# Autouke_Schematic.net
KiCad netlist of a schematic drawn in EAGLE
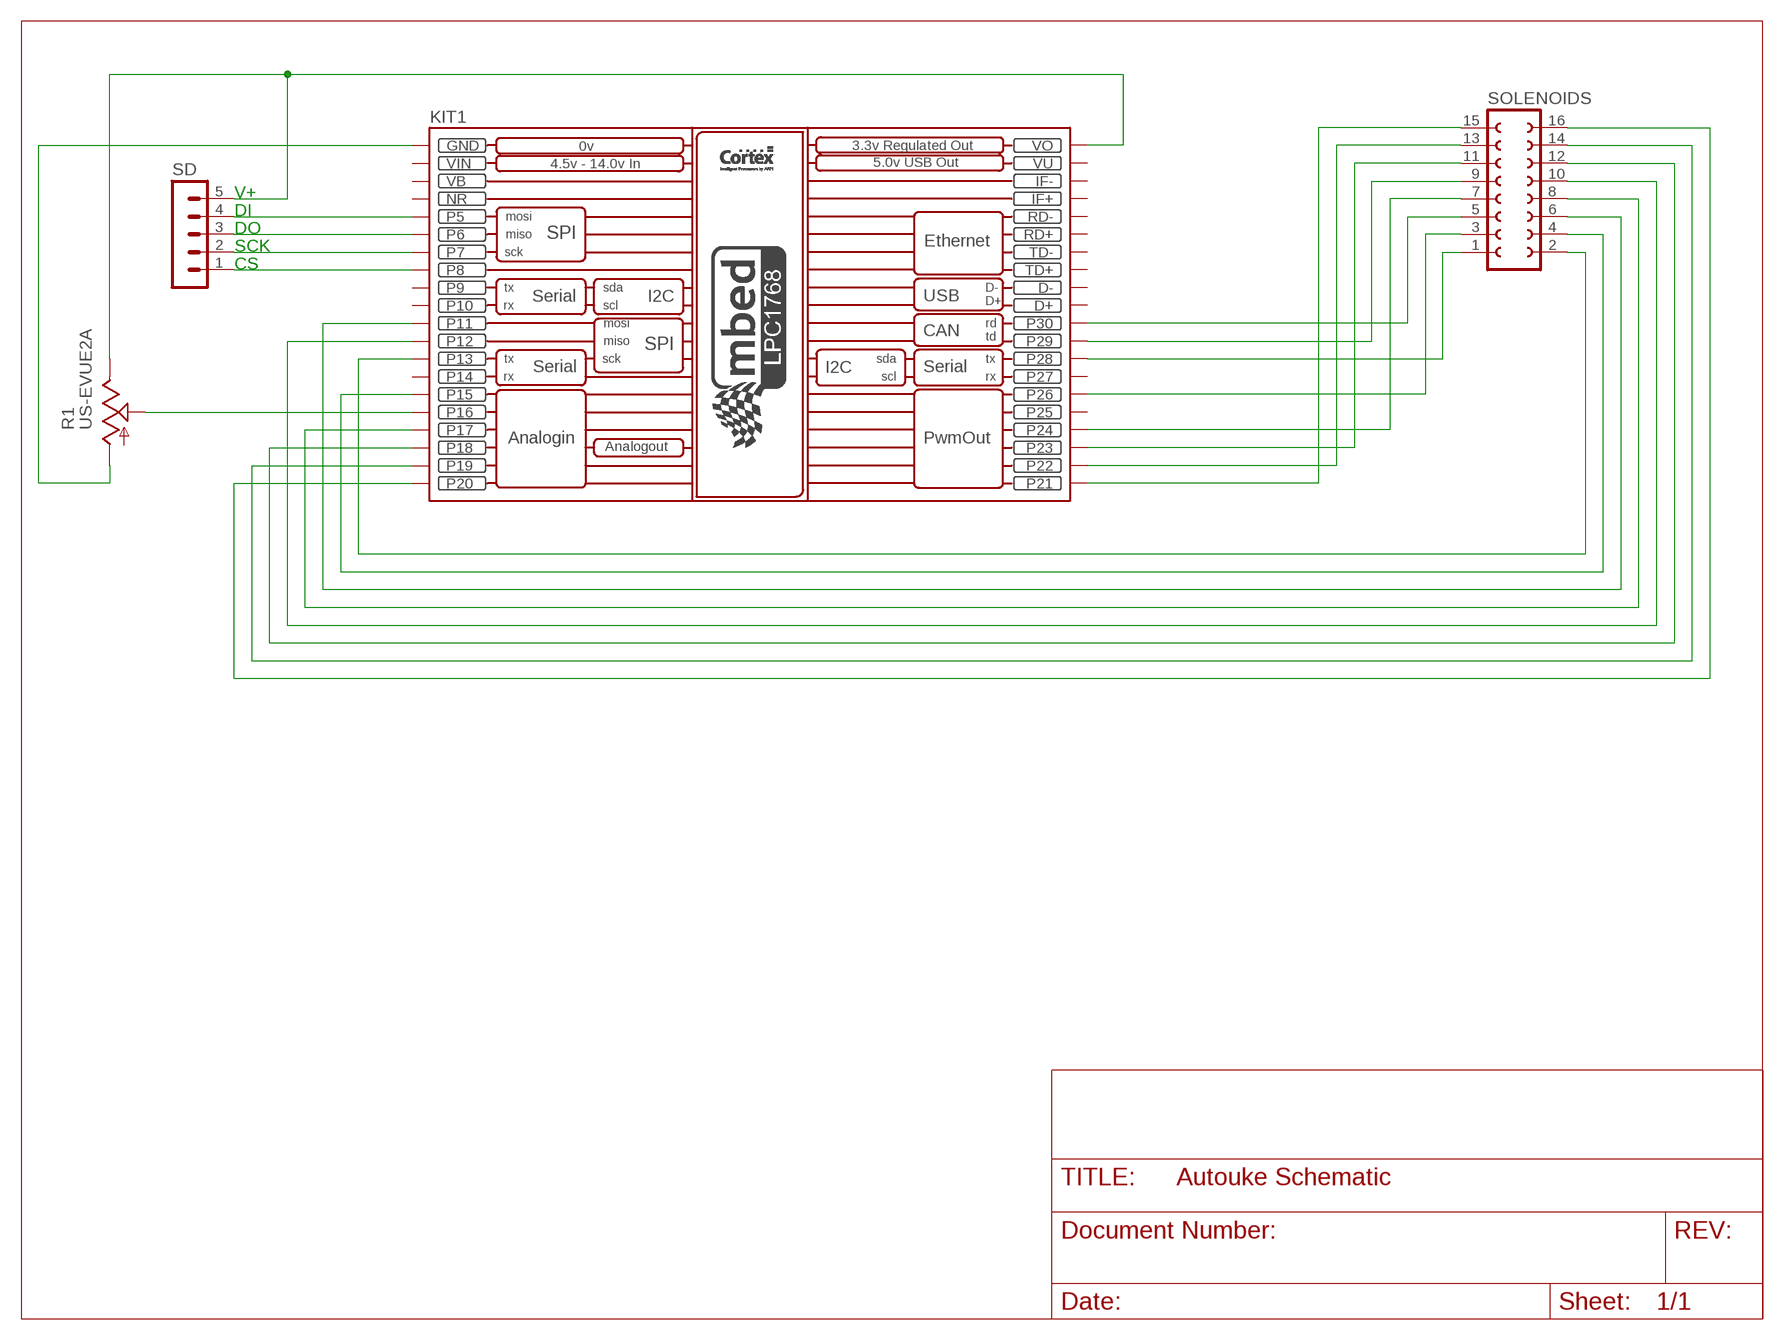
[diagram p0: schematic, sheet 1]

(export (version "E")
  (design (tool "Eeschema 10.0.6"))
  (components
    (comp (ref "KIT1")
      (value "MBED_NXP_LPC1768")
      (footprint "eagle-import:MBED-KIT")
      (libsource (lib "eagle-import") (part "MBED_NXP_LPC1768"))
    )
    (comp (ref "R1")
      (value "US-EVUE2A")
      (footprint "eagle-import:EVUE")
      (libsource (lib "eagle-import") (part "US-EVUE2A"))
    )
    (comp (ref "SD")
      (value "MA05-1")
      (footprint "eagle-import:MA05-1")
      (libsource (lib "eagle-import") (part "MA05-1"))
    )
    (comp (ref "SOLENOIDS")
      (value "FE08-2")
      (footprint "eagle-import:FE08-2")
      (libsource (lib "eagle-import") (part "FE08-2"))
    )
  )
  (nets
    (net (code "1") (name "/NR") (class "Default")
      (node (ref "KIT1") (pin "NR") (pinfunction "NR_NR") (pintype "power_in"))
    )
    (net (code "2") (name "/VB") (class "Default")
      (node (ref "KIT1") (pin "VB") (pinfunction "VB_VB") (pintype "power_in"))
    )
    (net (code "3") (name "/VIN") (class "Default")
      (node (ref "KIT1") (pin "VIN") (pinfunction "VIN_VIN") (pintype "power_in"))
    )
    (net (code "4") (name "/VU") (class "Default")
      (node (ref "KIT1") (pin "VU") (pinfunction "VU_VU") (pintype "power_in"))
    )
    (net (code "5") (name "Net-(KIT1-P5)") (class "Default")
      (node (ref "KIT1") (pin "P$5") (pinfunction "P5_P$5") (pintype "bidirectional"))
      (node (ref "SD") (pin "4") (pinfunction "4_4") (pintype "passive"))
    )
    (net (code "6") (name "Net-(KIT1-P6)") (class "Default")
      (node (ref "KIT1") (pin "P$6") (pinfunction "P6_P$6") (pintype "bidirectional"))
      (node (ref "SD") (pin "3") (pinfunction "3_3") (pintype "passive"))
    )
    (net (code "7") (name "Net-(KIT1-P7)") (class "Default")
      (node (ref "KIT1") (pin "P$7") (pinfunction "P7_P$7") (pintype "bidirectional"))
      (node (ref "SD") (pin "2") (pinfunction "2_2") (pintype "passive"))
    )
    (net (code "8") (name "Net-(KIT1-P8)") (class "Default")
      (node (ref "KIT1") (pin "P$8") (pinfunction "P8_P$8") (pintype "bidirectional"))
      (node (ref "SD") (pin "1") (pinfunction "1_1") (pintype "passive"))
    )
    (net (code "9") (name "Net-(KIT1-P11)") (class "Default")
      (node (ref "KIT1") (pin "P$11") (pinfunction "P11_P$11") (pintype "bidirectional"))
      (node (ref "SOLENOIDS") (pin "6") (pinfunction "6_6") (pintype "passive"))
    )
    (net (code "10") (name "Net-(KIT1-P12)") (class "Default")
      (node (ref "KIT1") (pin "P$12") (pinfunction "P12_P$12") (pintype "bidirectional"))
      (node (ref "SOLENOIDS") (pin "10") (pinfunction "10_10") (pintype "passive"))
    )
    (net (code "11") (name "Net-(KIT1-P13)") (class "Default")
      (node (ref "KIT1") (pin "P$13") (pinfunction "P13_P$13") (pintype "bidirectional"))
      (node (ref "SOLENOIDS") (pin "2") (pinfunction "2_2") (pintype "passive"))
    )
    (net (code "12") (name "Net-(KIT1-P15)") (class "Default")
      (node (ref "KIT1") (pin "P$15") (pinfunction "P15_P$15") (pintype "bidirectional"))
      (node (ref "SOLENOIDS") (pin "4") (pinfunction "4_4") (pintype "passive"))
    )
    (net (code "13") (name "Net-(KIT1-P16)") (class "Default")
      (node (ref "KIT1") (pin "P$16") (pinfunction "P16_P$16") (pintype "bidirectional"))
      (node (ref "R1") (pin "2") (pinfunction "S_2") (pintype "passive"))
    )
    (net (code "14") (name "Net-(KIT1-P17)") (class "Default")
      (node (ref "KIT1") (pin "P$17") (pinfunction "P17_P$17") (pintype "bidirectional"))
      (node (ref "SOLENOIDS") (pin "8") (pinfunction "8_8") (pintype "passive"))
    )
    (net (code "15") (name "Net-(KIT1-P18)") (class "Default")
      (node (ref "KIT1") (pin "P$18") (pinfunction "P18_P$18") (pintype "bidirectional"))
      (node (ref "SOLENOIDS") (pin "12") (pinfunction "12_12") (pintype "passive"))
    )
    (net (code "16") (name "Net-(KIT1-P19)") (class "Default")
      (node (ref "KIT1") (pin "P$19") (pinfunction "P19_P$19") (pintype "bidirectional"))
      (node (ref "SOLENOIDS") (pin "14") (pinfunction "14_14") (pintype "passive"))
    )
    (net (code "17") (name "Net-(KIT1-P20)") (class "Default")
      (node (ref "KIT1") (pin "P$20") (pinfunction "P20_P$20") (pintype "bidirectional"))
      (node (ref "SOLENOIDS") (pin "16") (pinfunction "16_16") (pintype "passive"))
    )
    (net (code "18") (name "Net-(KIT1-P21)") (class "Default")
      (node (ref "KIT1") (pin "P$21") (pinfunction "P21_P$21") (pintype "bidirectional"))
      (node (ref "SOLENOIDS") (pin "15") (pinfunction "15_15") (pintype "passive"))
    )
    (net (code "19") (name "Net-(KIT1-P22)") (class "Default")
      (node (ref "KIT1") (pin "P$22") (pinfunction "P22_P$22") (pintype "bidirectional"))
      (node (ref "SOLENOIDS") (pin "13") (pinfunction "13_13") (pintype "passive"))
    )
    (net (code "20") (name "Net-(KIT1-P23)") (class "Default")
      (node (ref "KIT1") (pin "P$23") (pinfunction "P23_P$23") (pintype "bidirectional"))
      (node (ref "SOLENOIDS") (pin "11") (pinfunction "11_11") (pintype "passive"))
    )
    (net (code "21") (name "Net-(KIT1-P24)") (class "Default")
      (node (ref "KIT1") (pin "P$24") (pinfunction "P24_P$24") (pintype "bidirectional"))
      (node (ref "SOLENOIDS") (pin "7") (pinfunction "7_7") (pintype "passive"))
    )
    (net (code "22") (name "Net-(KIT1-P26)") (class "Default")
      (node (ref "KIT1") (pin "P$26") (pinfunction "P26_P$26") (pintype "bidirectional"))
      (node (ref "SOLENOIDS") (pin "3") (pinfunction "3_3") (pintype "passive"))
    )
    (net (code "23") (name "Net-(KIT1-P28)") (class "Default")
      (node (ref "KIT1") (pin "P$28") (pinfunction "P28_P$28") (pintype "bidirectional"))
      (node (ref "SOLENOIDS") (pin "1") (pinfunction "1_1") (pintype "passive"))
    )
    (net (code "24") (name "Net-(KIT1-P29)") (class "Default")
      (node (ref "KIT1") (pin "P$29") (pinfunction "P29_P$29") (pintype "bidirectional"))
      (node (ref "SOLENOIDS") (pin "9") (pinfunction "9_9") (pintype "passive"))
    )
    (net (code "25") (name "Net-(KIT1-P30)") (class "Default")
      (node (ref "KIT1") (pin "P$30") (pinfunction "P30_P$30") (pintype "bidirectional"))
      (node (ref "SOLENOIDS") (pin "5") (pinfunction "5_5") (pintype "passive"))
    )
    (net (code "26") (name "Net-(KIT1-VO)") (class "Default")
      (node (ref "KIT1") (pin "VOUT") (pinfunction "VO_VOUT") (pintype "power_in"))
      (node (ref "R1") (pin "3") (pinfunction "E_3") (pintype "passive"))
      (node (ref "SD") (pin "5") (pinfunction "5_5") (pintype "passive"))
    )
    (net (code "27") (name "Net-(R1-A)") (class "Default")
      (node (ref "KIT1") (pin "GND") (pinfunction "GND_GND") (pintype "power_in"))
      (node (ref "R1") (pin "1") (pinfunction "A_1") (pintype "passive"))
    )
    (net (code "28") (name "unconnected-(KIT1-P9-PadP$9)") (class "Default")
      (node (ref "KIT1") (pin "P$9") (pinfunction "P9_P$9") (pintype "bidirectional"))
    )
    (net (code "29") (name "unconnected-(KIT1-P10-PadP$10)") (class "Default")
      (node (ref "KIT1") (pin "P$10") (pinfunction "P10_P$10") (pintype "bidirectional"))
    )
    (net (code "30") (name "unconnected-(KIT1-P14-PadP$14)") (class "Default")
      (node (ref "KIT1") (pin "P$14") (pinfunction "P14_P$14") (pintype "bidirectional"))
    )
    (net (code "31") (name "unconnected-(KIT1-P25-PadP$25)") (class "Default")
      (node (ref "KIT1") (pin "P$25") (pinfunction "P25_P$25") (pintype "bidirectional"))
    )
    (net (code "32") (name "unconnected-(KIT1-P27-PadP$27)") (class "Default")
      (node (ref "KIT1") (pin "P$27") (pinfunction "P27_P$27") (pintype "bidirectional"))
    )
    (net (code "33") (name "unconnected-(KIT1-PadD+)") (class "Default")
      (node (ref "KIT1") (pin "D+") (pinfunction "D+_D+") (pintype "bidirectional"))
    )
    (net (code "34") (name "unconnected-(KIT1-PadD-)") (class "Default")
      (node (ref "KIT1") (pin "D-") (pinfunction "D-_D-") (pintype "bidirectional"))
    )
    (net (code "35") (name "unconnected-(KIT1-PadIF+)") (class "Default")
      (node (ref "KIT1") (pin "IF+") (pinfunction "IF+_IF+") (pintype "bidirectional"))
    )
    (net (code "36") (name "unconnected-(KIT1-PadIF-)") (class "Default")
      (node (ref "KIT1") (pin "IF-") (pinfunction "IF-_IF-") (pintype "bidirectional"))
    )
    (net (code "37") (name "unconnected-(KIT1-PadRD+)") (class "Default")
      (node (ref "KIT1") (pin "RD+") (pinfunction "RD+_RD+") (pintype "bidirectional"))
    )
    (net (code "38") (name "unconnected-(KIT1-PadRD-)") (class "Default")
      (node (ref "KIT1") (pin "RD-") (pinfunction "RD-_RD-") (pintype "bidirectional"))
    )
    (net (code "39") (name "unconnected-(KIT1-PadTD+)") (class "Default")
      (node (ref "KIT1") (pin "TD+") (pinfunction "TD+_TD+") (pintype "bidirectional"))
    )
    (net (code "40") (name "unconnected-(KIT1-PadTD-)") (class "Default")
      (node (ref "KIT1") (pin "TD-") (pinfunction "TD-_TD-") (pintype "bidirectional"))
    )
  )
)
